# L298.net
KiCad netlist of a schematic drawn in Altium Designer
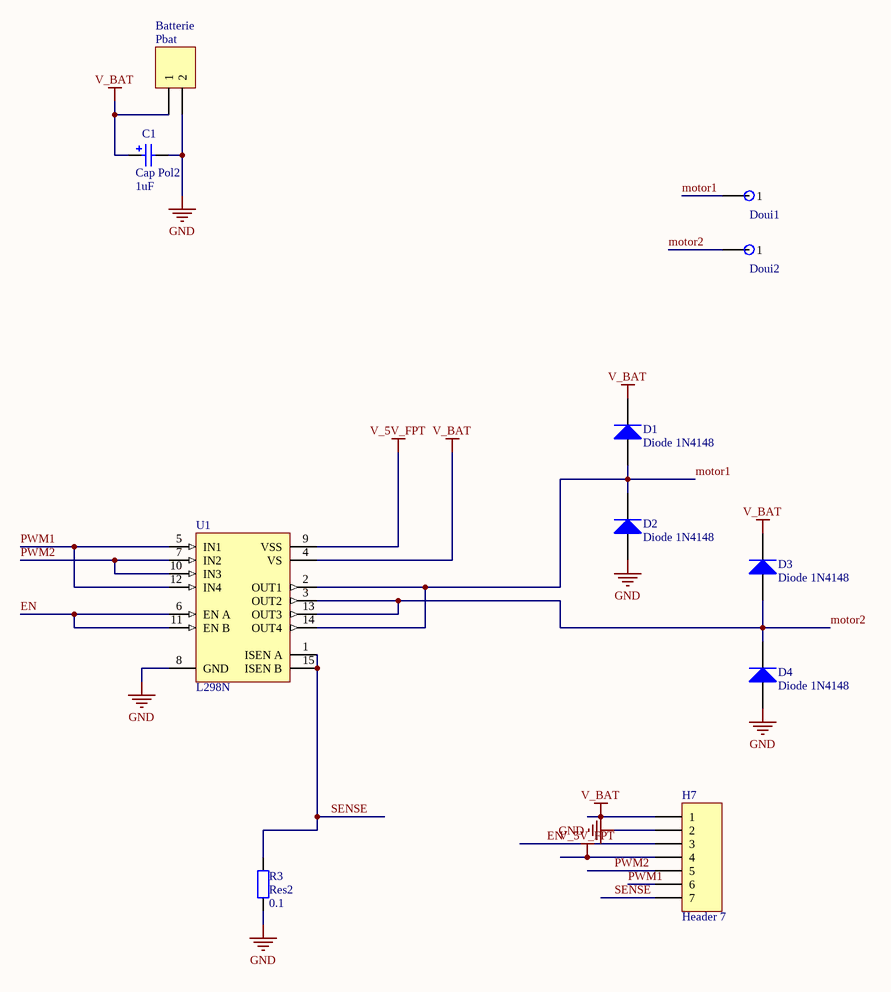
[diagram p0: L298.SchDoc]

(export (version "E")
  (design (tool "Eeschema 10.0.6"))
  (components
    (comp (ref "C1")
      (value "Cap Pol2")
      (footprint "Capa2_pol")
      (description "Polarized Capacitor (Radial)")
      (fields (field (name "ALTIUM_VALUE") "1uF") (field (name "PUBLISHER") "Altium Limited"))
      (libsource (lib "LIBRAIRIE_INTEGREE_PHELMA1") (part "Cap Pol2"))
    )
    (comp (ref "D1")
      (value "Diode 1N4148")
      (footprint "Ddiode")
      (description "High Conductance Fast Diode")
      (fields (field (name "PUBLISHER") "Altium Limited"))
      (libsource (lib "LIBRAIRIE_INTEGREE_PHELMA1") (part "Diode 1N4148"))
    )
    (comp (ref "D2")
      (value "Diode 1N4148")
      (footprint "Ddiode")
      (description "High Conductance Fast Diode")
      (fields (field (name "PUBLISHER") "Altium Limited"))
      (libsource (lib "LIBRAIRIE_INTEGREE_PHELMA1") (part "Diode 1N4148"))
    )
    (comp (ref "D3")
      (value "Diode 1N4148")
      (footprint "Ddiode")
      (description "High Conductance Fast Diode")
      (fields (field (name "PUBLISHER") "Altium Limited"))
      (libsource (lib "LIBRAIRIE_INTEGREE_PHELMA1") (part "Diode 1N4148"))
    )
    (comp (ref "D4")
      (value "Diode 1N4148")
      (footprint "Ddiode")
      (description "High Conductance Fast Diode")
      (fields (field (name "PUBLISHER") "Altium Limited"))
      (libsource (lib "LIBRAIRIE_INTEGREE_PHELMA1") (part "Diode 1N4148"))
    )
    (comp (ref "Doui1")
      (value "douille_2mm")
      (footprint "Douille-2mm")
      (description "1-Pin")
      (fields (field (name "PUBLISHER") "Altium Limited"))
      (libsource (lib "INTEGRATED_LIBRARY1_CONNECTEURS") (part "douille_2mm"))
    )
    (comp (ref "Doui2")
      (value "douille_2mm")
      (footprint "Douille-2mm")
      (description "1-Pin")
      (fields (field (name "PUBLISHER") "Altium Limited"))
      (libsource (lib "INTEGRATED_LIBRARY1_CONNECTEURS") (part "douille_2mm"))
    )
    (comp (ref "H7")
      (value "Header 7")
      (footprint "HDR1X7")
      (description "Header, 7-Pin")
      (fields (field (name "PUBLISHER") "Altium Limited"))
      (libsource (lib "Miscellaneous Connectors") (part "Header 7"))
    )
    (comp (ref "Pbat")
      (value "Batterie")
      (footprint "Bornier_2")
      (description "Header, 2-Pin")
      (fields (field (name "PUBLISHER") "Altium Limited"))
      (libsource (lib "INTEGRATED_LIBRARY1_CONNECTEURS") (part "Bornier_2"))
    )
    (comp (ref "R3")
      (value "Res2")
      (footprint "res5_1/4W")
      (description "Resistor")
      (fields (field (name "ALTIUM_VALUE") "0.1") (field (name "PUBLISHER") "Altium Limited"))
      (libsource (lib "LIBRAIRIE_INTEGREE_PHELMA1") (part "Res2"))
    )
    (comp (ref "U1")
      (value "L298N")
      (footprint "Multiwatt15V")
      (description "Dual Full Bridge Driver")
      (fields (field (name "PUBLISHER") "Altium Limited"))
      (libsource (lib "ST Interface DC Motor Controller") (part "L298N"))
    )
  )
  (nets
    (net (code "1") (name "/EN") (class "Default")
      (node (ref "H7") (pin "3") (pinfunction "3_3") (pintype "passive"))
      (node (ref "U1") (pin "11") (pinfunction "EN_B_11") (pintype "input"))
      (node (ref "U1") (pin "6") (pinfunction "EN_A_6") (pintype "input"))
    )
    (net (code "2") (name "/PWM1") (class "Default")
      (node (ref "H7") (pin "6") (pinfunction "6_6") (pintype "passive"))
      (node (ref "U1") (pin "12") (pinfunction "IN4_12") (pintype "input"))
      (node (ref "U1") (pin "5") (pinfunction "IN1_5") (pintype "input"))
    )
    (net (code "3") (name "/PWM2") (class "Default")
      (node (ref "H7") (pin "5") (pinfunction "5_5") (pintype "passive"))
      (node (ref "U1") (pin "10") (pinfunction "IN3_10") (pintype "input"))
      (node (ref "U1") (pin "7") (pinfunction "IN2_7") (pintype "input"))
    )
    (net (code "4") (name "/SENSE") (class "Default")
      (node (ref "H7") (pin "7") (pinfunction "7_7") (pintype "passive"))
      (node (ref "R3") (pin "1") (pinfunction "1_1") (pintype "passive"))
      (node (ref "U1") (pin "1") (pinfunction "ISEN_A_1") (pintype "passive"))
      (node (ref "U1") (pin "15") (pinfunction "ISEN_B_15") (pintype "passive"))
    )
    (net (code "5") (name "/motor1") (class "Default")
      (node (ref "D1") (pin "1") (pinfunction "A_1") (pintype "passive"))
      (node (ref "D2") (pin "2") (pinfunction "K_2") (pintype "passive"))
      (node (ref "Doui1") (pin "1") (pinfunction "1_1") (pintype "passive"))
      (node (ref "U1") (pin "14") (pinfunction "OUT4_14") (pintype "output"))
      (node (ref "U1") (pin "2") (pinfunction "OUT1_2") (pintype "output"))
    )
    (net (code "6") (name "/motor2") (class "Default")
      (node (ref "D3") (pin "1") (pinfunction "A_1") (pintype "passive"))
      (node (ref "D4") (pin "2") (pinfunction "K_2") (pintype "passive"))
      (node (ref "Doui2") (pin "1") (pinfunction "1_1") (pintype "passive"))
      (node (ref "U1") (pin "13") (pinfunction "OUT3_13") (pintype "output"))
      (node (ref "U1") (pin "3") (pinfunction "OUT2_3") (pintype "output"))
    )
    (net (code "7") (name "GND") (class "Default")
      (node (ref "C1") (pin "2") (pinfunction "2_2") (pintype "passive"))
      (node (ref "D2") (pin "1") (pinfunction "A_1") (pintype "passive"))
      (node (ref "D4") (pin "1") (pinfunction "A_1") (pintype "passive"))
      (node (ref "H7") (pin "2") (pinfunction "2_2") (pintype "passive"))
      (node (ref "Pbat") (pin "2") (pinfunction "2_2") (pintype "passive"))
      (node (ref "R3") (pin "2") (pinfunction "2_2") (pintype "passive"))
      (node (ref "U1") (pin "8") (pinfunction "GND_8") (pintype "power_in"))
    )
    (net (code "8") (name "V_5V_FPT") (class "Default")
      (node (ref "H7") (pin "4") (pinfunction "4_4") (pintype "passive"))
      (node (ref "U1") (pin "9") (pinfunction "VSS_9") (pintype "power_in"))
    )
    (net (code "9") (name "V_BAT") (class "Default")
      (node (ref "C1") (pin "1") (pinfunction "1_1") (pintype "passive"))
      (node (ref "D1") (pin "2") (pinfunction "K_2") (pintype "passive"))
      (node (ref "D3") (pin "2") (pinfunction "K_2") (pintype "passive"))
      (node (ref "H7") (pin "1") (pinfunction "1_1") (pintype "passive"))
      (node (ref "Pbat") (pin "1") (pinfunction "1_1") (pintype "passive"))
      (node (ref "U1") (pin "4") (pinfunction "VS_4") (pintype "power_in"))
    )
  )
)
